# contactor_single.net
KiCad netlist of a schematic drawn in Altium Designer
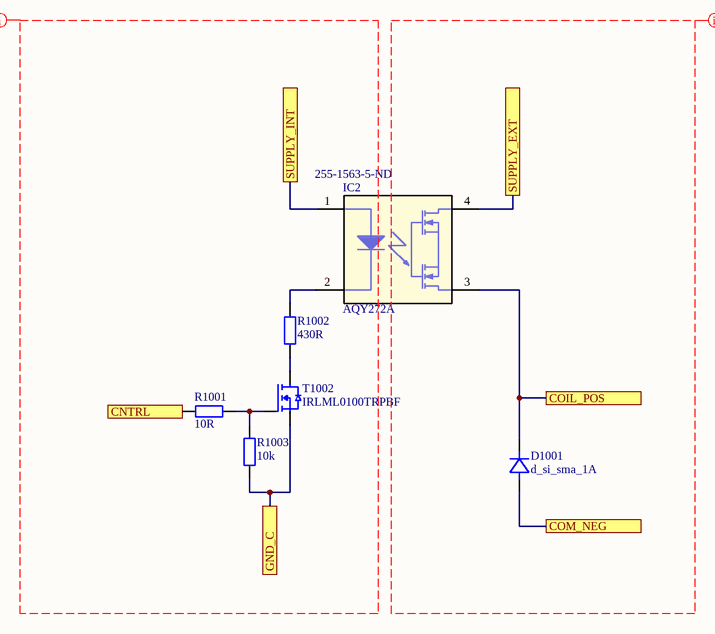
[diagram p0: contactor_single.SchDoc]

(export (version "E")
  (design (tool "Eeschema 10.0.6"))
  (components
    (comp (ref "D1001")
      (value "d_si_sma_1A")
      (footprint "DIOM4326X24N")
      (description "Standard Recovery Diode, 100 V, 1 A, Single, 1 V, 2 µs, 30 A")
      (fields (field (name "MANUFACTURER") "ON Semiconductor"))
      (libsource (lib "OE750") (part "D"))
    )
    (comp (ref "IC2")
      (value "AQY272A")
      (footprint "AQY27_PDIP_SMD")
      (fields
        (field (name "MANUFACTURER") "Panasonic")
        (field (name "SUPPLIER PART NUMBER 1") "255-1563-5-ND")
      )
      (libsource (lib "master-010106") (part "AQY272A"))
    )
    (comp (ref "R1001")
      (value "10R")
      (footprint "0603R")
      (description "SMD Resistor 10R 0603")
      (fields (field (name "PART NUMBER") "gen_R_10R_0603") (field (name "TOLERANCE") "1%"))
      (libsource (lib "master-010106") (part "R"))
    )
    (comp (ref "R1002")
      (value "430R")
      (footprint "0603R")
      (description "SMD Resistor 430R 0603")
      (fields (field (name "PART NUMBER") "gen_R_430R_0603") (field (name "TOLERANCE") "1%"))
      (libsource (lib "master-010106") (part "R"))
    )
    (comp (ref "R1003")
      (value "10k")
      (footprint "0603R")
      (description "SMD Resistor 10k 0603")
      (fields (field (name "PART NUMBER") "gen_R_10k_0603") (field (name "TOLERANCE") "1%"))
      (libsource (lib "master-010106") (part "R"))
    )
    (comp (ref "T1002")
      (value "IRLML0100TRPBF")
      (footprint "SOT95P237X110-3N")
      (description "MOSFET-Transistor, n-Kanal, 1.6 A, 100 V, 0.178 ohm, 10 V, 2.5 V")
      (fields (field (name "MANUFACTURER") "Infineon"))
      (libsource (lib "OE750") (part "NMOS"))
    )
  )
  (nets
    (net (code "1") (name "/CNTRL") (class "Default")
      (node (ref "R1001") (pin "2") (pinfunction "2_2") (pintype "passive"))
    )
    (net (code "2") (name "/COIL_POS") (class "Default")
      (node (ref "D1001") (pin "1") (pinfunction "K_1") (pintype "passive"))
      (node (ref "IC2") (pin "3") (pinfunction "3_3") (pintype "passive"))
    )
    (net (code "3") (name "/COM_NEG") (class "Default")
      (node (ref "D1001") (pin "2") (pinfunction "A_2") (pintype "passive"))
    )
    (net (code "4") (name "/GND_C") (class "Default")
      (node (ref "R1003") (pin "1") (pinfunction "1_1") (pintype "passive"))
      (node (ref "T1002") (pin "S") (pinfunction "S_S") (pintype "passive"))
    )
    (net (code "5") (name "/SUPPLY_EXT") (class "Default")
      (node (ref "IC2") (pin "4") (pinfunction "4_4") (pintype "passive"))
    )
    (net (code "6") (name "/SUPPLY_INT") (class "Default")
      (node (ref "IC2") (pin "1") (pinfunction "1_1") (pintype "passive"))
    )
    (net (code "7") (name "Net-(IC2-Pad2)") (class "Default")
      (node (ref "IC2") (pin "2") (pinfunction "2_2") (pintype "passive"))
      (node (ref "R1002") (pin "2") (pinfunction "2_2") (pintype "passive"))
    )
    (net (code "8") (name "Net-(R1001-Pad1)") (class "Default")
      (node (ref "R1001") (pin "1") (pinfunction "1_1") (pintype "passive"))
      (node (ref "R1003") (pin "2") (pinfunction "2_2") (pintype "passive"))
      (node (ref "T1002") (pin "G") (pinfunction "G_G") (pintype "passive"))
    )
    (net (code "9") (name "Net-(R1002-Pad1)") (class "Default")
      (node (ref "R1002") (pin "1") (pinfunction "1_1") (pintype "passive"))
      (node (ref "T1002") (pin "D") (pinfunction "D_D") (pintype "passive"))
    )
  )
)
